# Sheet1.net
KiCad netlist of a schematic drawn in Altium Designer
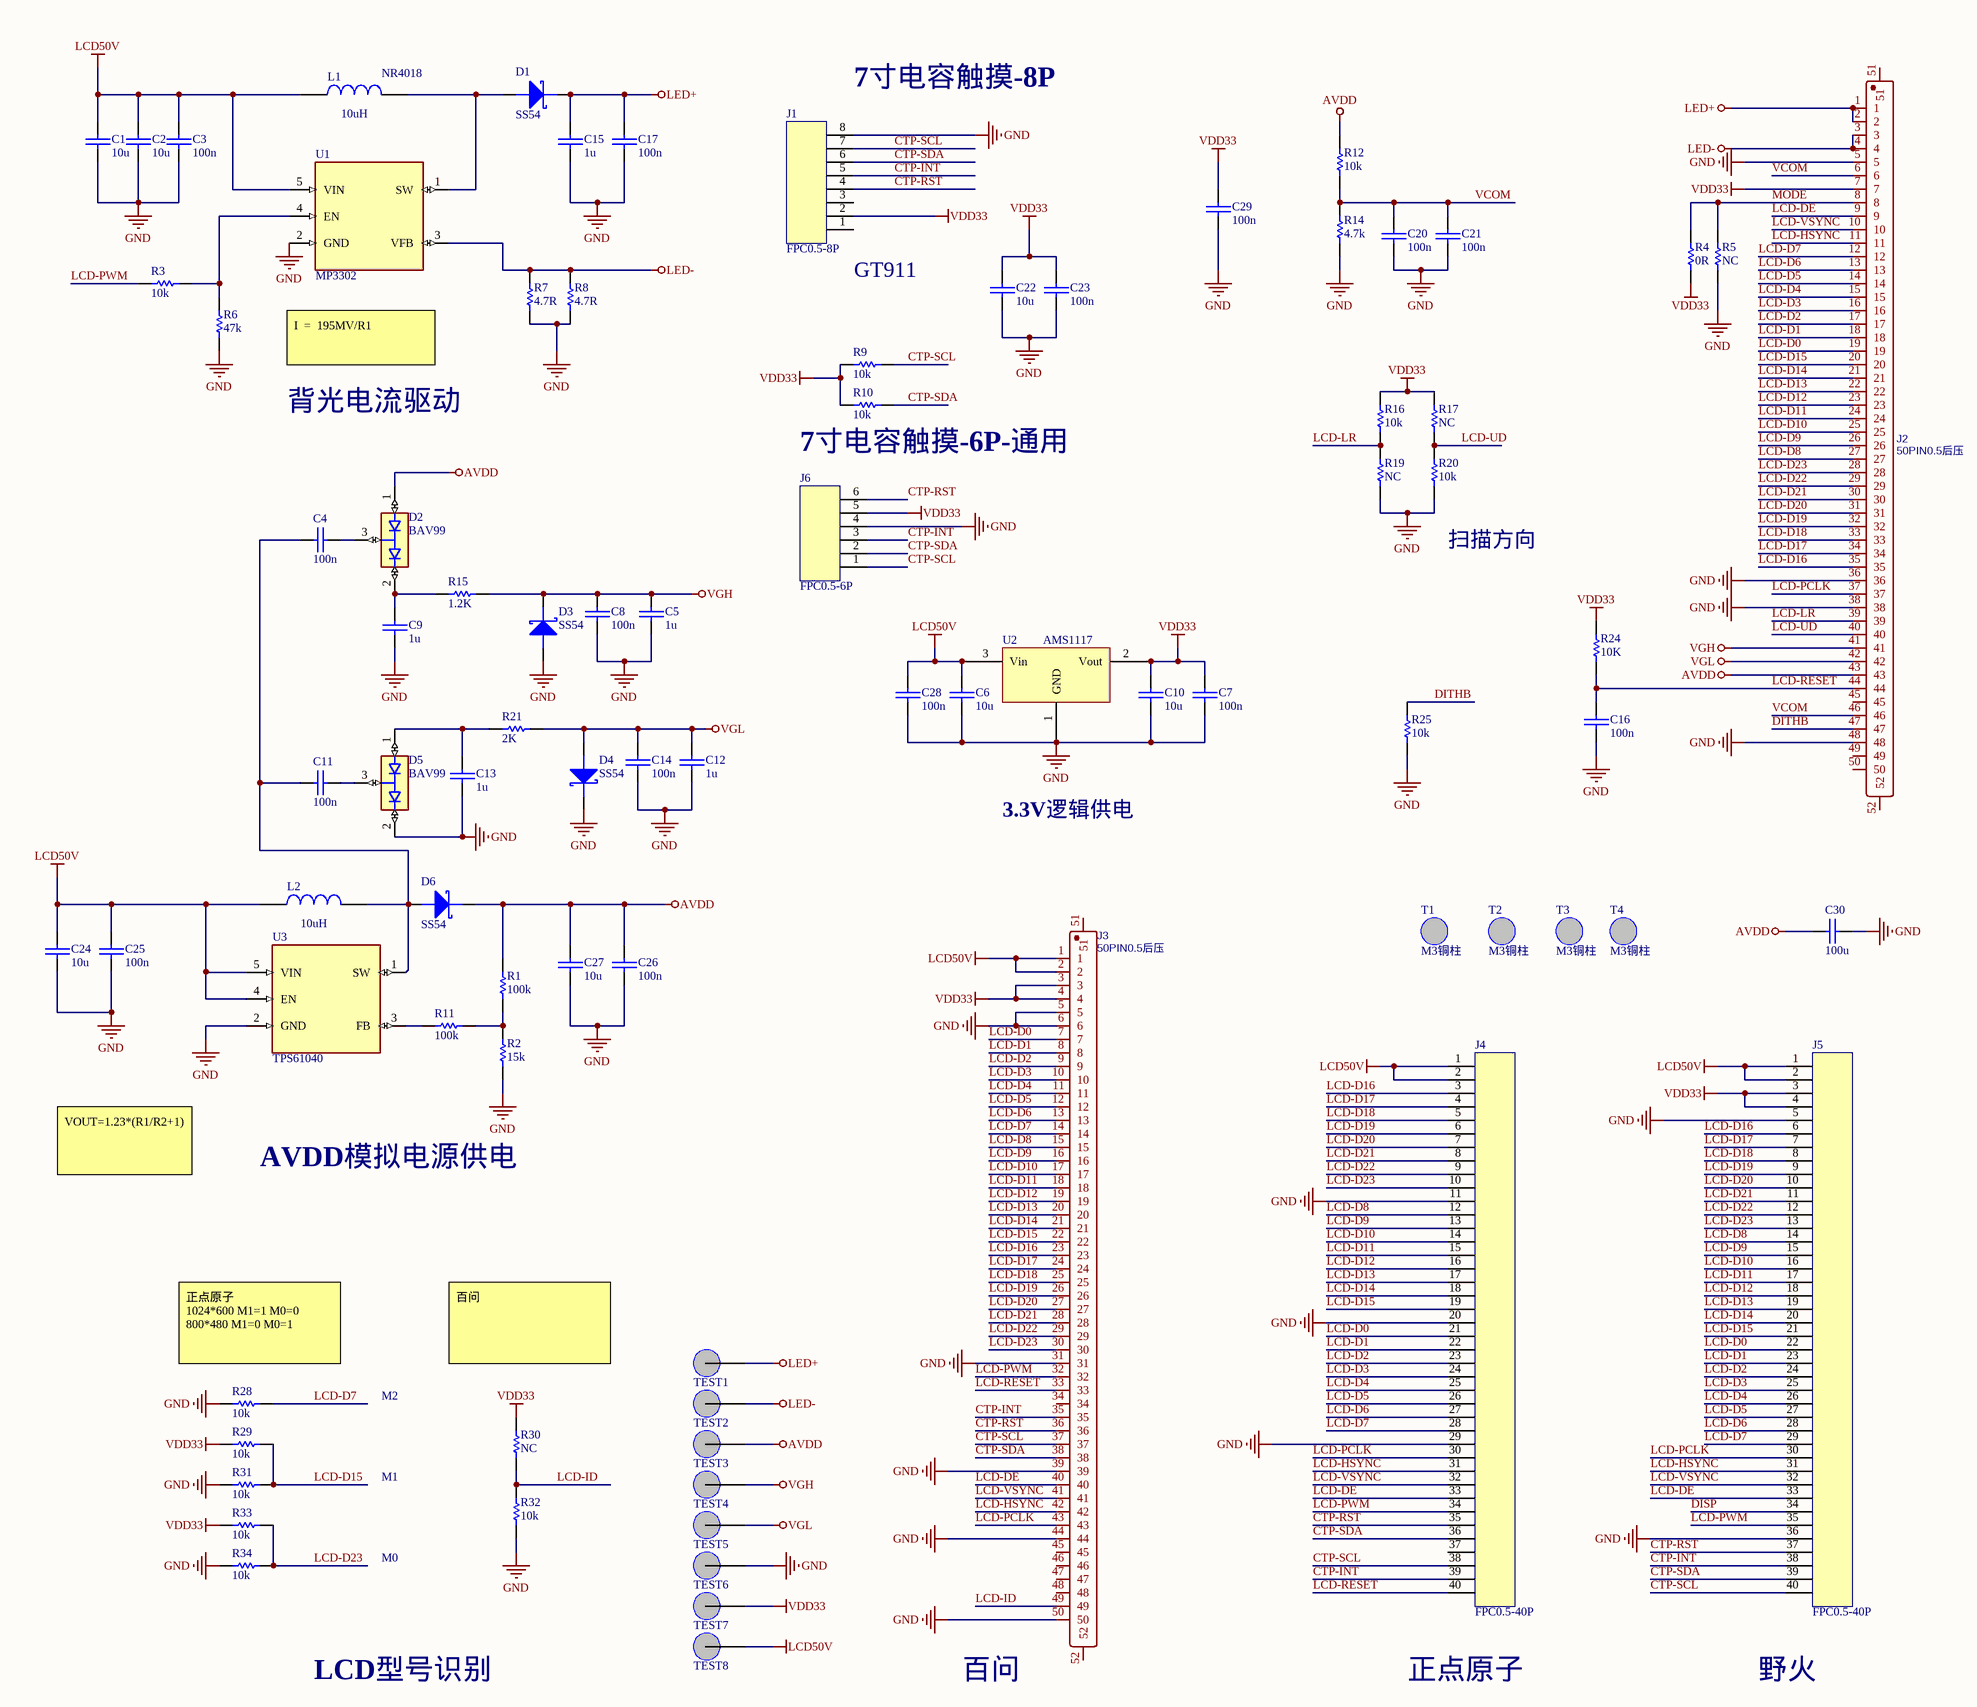
[diagram p0: Sheet1.SchDoc]

(export (version "E")
  (design (tool "Eeschema 10.0.6"))
  (components
    (comp (ref "C1")
      (value "10u")
      (footprint "0603C")
      (description "无极性电容")
      (libsource (lib "常用元件-电容") (part "CAP"))
    )
    (comp (ref "C2")
      (value "10u")
      (footprint "0603C")
      (description "无极性电容")
      (libsource (lib "常用元件-电容") (part "CAP"))
    )
    (comp (ref "C3")
      (value "100n")
      (footprint "0603C")
      (description "无极性电容")
      (libsource (lib "常用元件-电容") (part "CAP"))
    )
    (comp (ref "C4")
      (value "100n")
      (footprint "0603C")
      (description "无极性电容")
      (libsource (lib "常用元件-电容") (part "CAP"))
    )
    (comp (ref "C5")
      (value "1u")
      (footprint "0603C")
      (description "无极性电容")
      (libsource (lib "常用元件-电容") (part "CAP"))
    )
    (comp (ref "C6")
      (value "10u")
      (footprint "0603C")
      (description "无极性电容")
      (libsource (lib "常用元件-电容") (part "CAP"))
    )
    (comp (ref "C7")
      (value "100n")
      (footprint "0603C")
      (description "无极性电容")
      (libsource (lib "常用元件-电容") (part "CAP"))
    )
    (comp (ref "C8")
      (value "100n")
      (footprint "0603C")
      (description "无极性电容")
      (libsource (lib "常用元件-电容") (part "CAP"))
    )
    (comp (ref "C9")
      (value "1u")
      (footprint "0603C")
      (description "无极性电容")
      (libsource (lib "常用元件-电容") (part "CAP"))
    )
    (comp (ref "C10")
      (value "10u")
      (footprint "0603C")
      (description "无极性电容")
      (libsource (lib "常用元件-电容") (part "CAP"))
    )
    (comp (ref "C11")
      (value "100n")
      (footprint "0603C")
      (description "无极性电容")
      (libsource (lib "常用元件-电容") (part "CAP"))
    )
    (comp (ref "C12")
      (value "1u")
      (footprint "0603C")
      (description "无极性电容")
      (libsource (lib "常用元件-电容") (part "CAP"))
    )
    (comp (ref "C13")
      (value "1u")
      (footprint "0603C")
      (description "无极性电容")
      (libsource (lib "常用元件-电容") (part "CAP"))
    )
    (comp (ref "C14")
      (value "100n")
      (footprint "0603C")
      (description "无极性电容")
      (libsource (lib "常用元件-电容") (part "CAP"))
    )
    (comp (ref "C15")
      (value "1u")
      (footprint "0603C")
      (description "无极性电容")
      (libsource (lib "常用元件-电容") (part "CAP"))
    )
    (comp (ref "C16")
      (value "100n")
      (footprint "0603C")
      (description "无极性电容")
      (libsource (lib "常用元件-电容") (part "CAP"))
    )
    (comp (ref "C17")
      (value "100n")
      (footprint "0603C")
      (description "无极性电容")
      (libsource (lib "常用元件-电容") (part "CAP"))
    )
    (comp (ref "C20")
      (value "100n")
      (footprint "0603C")
      (description "无极性电容")
      (libsource (lib "常用元件-电容") (part "CAP"))
    )
    (comp (ref "C21")
      (value "100n")
      (footprint "0603C")
      (description "无极性电容")
      (libsource (lib "常用元件-电容") (part "CAP"))
    )
    (comp (ref "C22")
      (value "10u")
      (footprint "0603C")
      (description "无极性电容")
      (libsource (lib "常用元件-电容") (part "CAP"))
    )
    (comp (ref "C23")
      (value "100n")
      (footprint "0603C")
      (description "无极性电容")
      (libsource (lib "常用元件-电容") (part "CAP"))
    )
    (comp (ref "C24")
      (value "10u")
      (footprint "0603C")
      (description "无极性电容")
      (libsource (lib "常用元件-电容") (part "CAP"))
    )
    (comp (ref "C25")
      (value "100n")
      (footprint "0603C")
      (description "无极性电容")
      (libsource (lib "常用元件-电容") (part "CAP"))
    )
    (comp (ref "C26")
      (value "100n")
      (footprint "0603C")
      (description "无极性电容")
      (libsource (lib "常用元件-电容") (part "CAP"))
    )
    (comp (ref "C27")
      (value "10u")
      (footprint "0603C")
      (description "无极性电容")
      (libsource (lib "常用元件-电容") (part "CAP"))
    )
    (comp (ref "C28")
      (value "100n")
      (footprint "0603C")
      (description "无极性电容")
      (libsource (lib "常用元件-电容") (part "CAP"))
    )
    (comp (ref "C29")
      (value "100n")
      (footprint "0603C")
      (description "无极性电容")
      (libsource (lib "常用元件-电容") (part "CAP"))
    )
    (comp (ref "C30")
      (value "100u")
      (footprint "0603C")
      (description "无极性电容")
      (libsource (lib "常用元件-电容") (part "CAP"))
    )
    (comp (ref "D1")
      (value "SS54")
      (footprint "SOD-123")
      (description "肖特基二极管")
      (libsource (lib "常用元件-二极管") (part "DIODE SCHOTTKY"))
    )
    (comp (ref "D2")
      (value "BAV99")
      (footprint "BAV99:SOT23-3")
      (fields (field (name "MF") "{'manufacturer': u'ON Semiconductor'}"))
      (libsource (lib "*") (part "BAV99"))
    )
    (comp (ref "D3")
      (value "SS54")
      (footprint "SOD-123")
      (description "肖特基二极管")
      (libsource (lib "常用元件-二极管") (part "DIODE SCHOTTKY"))
    )
    (comp (ref "D4")
      (value "SS54")
      (footprint "SOD-123")
      (description "肖特基二极管")
      (libsource (lib "常用元件-二极管") (part "DIODE SCHOTTKY"))
    )
    (comp (ref "D5")
      (value "BAV99")
      (footprint "BAV99:SOT23-3")
      (fields (field (name "MF") "{'manufacturer': u'ON Semiconductor'}"))
      (libsource (lib "*") (part "BAV99"))
    )
    (comp (ref "D6")
      (value "SS54")
      (footprint "SOD-123")
      (description "肖特基二极管")
      (libsource (lib "常用元件-二极管") (part "DIODE SCHOTTKY"))
    )
    (comp (ref "J1")
      (value "FPC0.5-8P")
      (footprint "FPC0.5-8P")
      (description "贴片")
      (libsource (lib "插接类-FPC") (part "FPC0.5-8P"))
    )
    (comp (ref "J2")
      (value "50PIN0.5后压")
      (footprint "FPC-SMD_KH-FG0.5-H2.0-50PIN")
      (fields (field (name "BOM_SUPPLIER PART") "C9900011403") (field (name "CONTRIBUTOR") "LCSC"))
      (libsource (lib "altium-import") (part "root_0_50PIN0.5后压_"))
    )
    (comp (ref "J3")
      (value "50PIN0.5后压")
      (footprint "FPC-SMD_KH-FG0.5-H2.0-50PIN")
      (fields (field (name "BOM_SUPPLIER PART") "C9900011403") (field (name "CONTRIBUTOR") "LCSC"))
      (libsource (lib "altium-import") (part "root_0_50PIN0.5后压_"))
    )
    (comp (ref "J4")
      (value "FPC0.5-40P")
      (footprint "FPC0.5-40P")
      (description "贴片")
      (libsource (lib "插接类-FPC") (part "FPC0.5-40P"))
    )
    (comp (ref "J5")
      (value "FPC0.5-40P")
      (footprint "FPC0.5-40P")
      (description "贴片")
      (libsource (lib "插接类-FPC") (part "FPC0.5-40P"))
    )
    (comp (ref "J6")
      (value "FPC0.5-6P")
      (footprint "FPC0.5-6P")
      (description "贴片")
      (libsource (lib "插接类-FPC") (part "FPC0.5-6P"))
    )
    (comp (ref "L1")
      (value "10uH")
      (footprint "CD42")
      (description "INDUCTOR")
      (libsource (lib "常用元件-电感") (part "INDUCTOR"))
    )
    (comp (ref "L2")
      (value "10uH")
      (footprint "CD42")
      (description "INDUCTOR")
      (libsource (lib "常用元件-电感") (part "INDUCTOR"))
    )
    (comp (ref "R1") (value "100k") (footprint "0603R") (libsource (lib "常用元件-电阻") (part "RES")))
    (comp (ref "R2") (value "15k") (footprint "0603R") (libsource (lib "常用元件-电阻") (part "RES")))
    (comp (ref "R3") (value "10k") (footprint "0603R") (libsource (lib "常用元件-电阻") (part "RES")))
    (comp (ref "R4") (value "0R") (footprint "0603R") (libsource (lib "常用元件-电阻") (part "RES")))
    (comp (ref "R5") (value "NC") (footprint "0603R") (libsource (lib "常用元件-电阻") (part "RES")))
    (comp (ref "R6") (value "47k") (footprint "0603R") (libsource (lib "常用元件-电阻") (part "RES")))
    (comp (ref "R7") (value "4.7R") (footprint "0603R") (libsource (lib "常用元件-电阻") (part "RES")))
    (comp (ref "R8") (value "4.7R") (footprint "0603R") (libsource (lib "常用元件-电阻") (part "RES")))
    (comp (ref "R9") (value "10k") (footprint "0603R") (libsource (lib "常用元件-电阻") (part "RES")))
    (comp (ref "R10") (value "10k") (footprint "0603R") (libsource (lib "常用元件-电阻") (part "RES")))
    (comp (ref "R11") (value "100k") (footprint "0603R") (libsource (lib "常用元件-电阻") (part "RES")))
    (comp (ref "R12") (value "10k") (footprint "0603R") (libsource (lib "常用元件-电阻") (part "RES")))
    (comp (ref "R14") (value "4.7k") (footprint "0603R") (libsource (lib "常用元件-电阻") (part "RES")))
    (comp (ref "R15") (value "1.2K") (footprint "0603R") (libsource (lib "常用元件-电阻") (part "RES")))
    (comp (ref "R16") (value "10k") (footprint "0603R") (libsource (lib "常用元件-电阻") (part "RES")))
    (comp (ref "R17") (value "NC") (footprint "0603R") (libsource (lib "常用元件-电阻") (part "RES")))
    (comp (ref "R19") (value "NC") (footprint "0603R") (libsource (lib "常用元件-电阻") (part "RES")))
    (comp (ref "R20") (value "10k") (footprint "0603R") (libsource (lib "常用元件-电阻") (part "RES")))
    (comp (ref "R21") (value "2K") (footprint "0603R") (libsource (lib "常用元件-电阻") (part "RES")))
    (comp (ref "R24") (value "10K") (footprint "0603R") (libsource (lib "常用元件-电阻") (part "RES")))
    (comp (ref "R25") (value "10k") (footprint "0603R") (libsource (lib "常用元件-电阻") (part "RES")))
    (comp (ref "R28") (value "10k") (footprint "0603R") (libsource (lib "常用元件-电阻") (part "RES")))
    (comp (ref "R29") (value "10k") (footprint "0603R") (libsource (lib "常用元件-电阻") (part "RES")))
    (comp (ref "R30") (value "NC") (footprint "0603R") (libsource (lib "常用元件-电阻") (part "RES")))
    (comp (ref "R31") (value "10k") (footprint "0603R") (libsource (lib "常用元件-电阻") (part "RES")))
    (comp (ref "R32") (value "10k") (footprint "0603R") (libsource (lib "常用元件-电阻") (part "RES")))
    (comp (ref "R33") (value "10k") (footprint "0603R") (libsource (lib "常用元件-电阻") (part "RES")))
    (comp (ref "R34") (value "10k") (footprint "0603R") (libsource (lib "常用元件-电阻") (part "RES")))
    (comp (ref "T1") (value "M3铜柱") (footprint "M3 单孔") (libsource (lib "M3铜柱") (part "M3铜柱")))
    (comp (ref "T2") (value "M3铜柱") (footprint "M3 单孔") (libsource (lib "M3铜柱") (part "M3铜柱")))
    (comp (ref "T3") (value "M3铜柱") (footprint "M3 单孔") (libsource (lib "M3铜柱") (part "M3铜柱")))
    (comp (ref "T4") (value "M3铜柱") (footprint "M3 单孔") (libsource (lib "M3铜柱") (part "M3铜柱")))
    (comp (ref "TEST1")
      (value "TEST")
      (footprint "TEST TP1.4_G")
      (description "测试针")
      (fields (field (name "版权归属") "源创客"))
      (libsource (lib "测试类-测试针") (part "TEST"))
    )
    (comp (ref "TEST2")
      (value "TEST")
      (footprint "TEST TP1.4_G")
      (description "测试针")
      (fields (field (name "版权归属") "源创客"))
      (libsource (lib "测试类-测试针") (part "TEST"))
    )
    (comp (ref "TEST3")
      (value "TEST")
      (footprint "TEST TP1.4_G")
      (description "测试针")
      (fields (field (name "版权归属") "源创客"))
      (libsource (lib "测试类-测试针") (part "TEST"))
    )
    (comp (ref "TEST4")
      (value "TEST")
      (footprint "TEST TP1.4_G")
      (description "测试针")
      (fields (field (name "版权归属") "源创客"))
      (libsource (lib "测试类-测试针") (part "TEST"))
    )
    (comp (ref "TEST5")
      (value "TEST")
      (footprint "TEST TP1.4_G")
      (description "测试针")
      (fields (field (name "版权归属") "源创客"))
      (libsource (lib "测试类-测试针") (part "TEST"))
    )
    (comp (ref "TEST6")
      (value "TEST")
      (footprint "TEST TP1.4_G")
      (description "测试针")
      (fields (field (name "版权归属") "源创客"))
      (libsource (lib "测试类-测试针") (part "TEST"))
    )
    (comp (ref "TEST7")
      (value "TEST")
      (footprint "TEST TP1.4_G")
      (description "测试针")
      (fields (field (name "版权归属") "源创客"))
      (libsource (lib "测试类-测试针") (part "TEST"))
    )
    (comp (ref "TEST8")
      (value "TEST")
      (footprint "TEST TP1.4_G")
      (description "测试针")
      (fields (field (name "版权归属") "源创客"))
      (libsource (lib "测试类-测试针") (part "TEST"))
    )
    (comp (ref "U1")
      (value "MP3302")
      (footprint "SOT95P280X100-5N")
      (fields
        (field (name "MP") "TPS563201DDCR")
        (field (name "MF") "{'manufacturer': u'Texas Instruments'}")
      )
      (libsource (lib "MP3302") (part "MP3302"))
    )
    (comp (ref "U2")
      (value "AMS1117")
      (footprint "SOT223")
      (description "三端稳压芯片")
      (libsource (lib "芯片-电源芯片") (part "AMS1117"))
    )
    (comp (ref "U3")
      (value "TPS61040")
      (footprint "SOT95P280X100-5N")
      (fields
        (field (name "MP") "TPS563201DDCR")
        (field (name "MF") "{'manufacturer': u'Texas Instruments'}")
      )
      (libsource (lib "MP1541") (part "MP1541"))
    )
  )
  (nets
    (net (code "1") (name "/CTP-INT") (class "Default")
      (node (ref "J1") (pin "5") (pinfunction "5_5") (pintype "passive"))
      (node (ref "J3") (pin "35") (pinfunction "35_35") (pintype "passive"))
      (node (ref "J4") (pin "39") (pinfunction "39_39") (pintype "passive"))
      (node (ref "J5") (pin "38") (pinfunction "38_38") (pintype "passive"))
      (node (ref "J6") (pin "3") (pinfunction "3_3") (pintype "passive"))
    )
    (net (code "2") (name "/CTP-RST") (class "Default")
      (node (ref "J1") (pin "4") (pinfunction "4_4") (pintype "passive"))
      (node (ref "J3") (pin "36") (pinfunction "36_36") (pintype "passive"))
      (node (ref "J4") (pin "35") (pinfunction "35_35") (pintype "passive"))
      (node (ref "J5") (pin "37") (pinfunction "37_37") (pintype "passive"))
      (node (ref "J6") (pin "6") (pinfunction "6_6") (pintype "passive"))
    )
    (net (code "3") (name "/CTP-SCL") (class "Default")
      (node (ref "J1") (pin "7") (pinfunction "7_7") (pintype "passive"))
      (node (ref "J3") (pin "37") (pinfunction "37_37") (pintype "passive"))
      (node (ref "J4") (pin "38") (pinfunction "38_38") (pintype "passive"))
      (node (ref "J5") (pin "40") (pinfunction "40_40") (pintype "passive"))
      (node (ref "J6") (pin "1") (pinfunction "1_1") (pintype "passive"))
      (node (ref "R9") (pin "1") (pinfunction "1_1") (pintype "passive"))
    )
    (net (code "4") (name "/CTP-SDA") (class "Default")
      (node (ref "J1") (pin "6") (pinfunction "6_6") (pintype "passive"))
      (node (ref "J3") (pin "38") (pinfunction "38_38") (pintype "passive"))
      (node (ref "J4") (pin "36") (pinfunction "36_36") (pintype "passive"))
      (node (ref "J5") (pin "39") (pinfunction "39_39") (pintype "passive"))
      (node (ref "J6") (pin "2") (pinfunction "2_2") (pintype "passive"))
      (node (ref "R10") (pin "1") (pinfunction "1_1") (pintype "passive"))
    )
    (net (code "5") (name "/DISP") (class "Default")
      (node (ref "J5") (pin "34") (pinfunction "34_34") (pintype "passive"))
    )
    (net (code "6") (name "/DITHB") (class "Default")
      (node (ref "J2") (pin "47") (pinfunction "47_47") (pintype "passive"))
      (node (ref "R25") (pin "1") (pinfunction "1_1") (pintype "passive"))
    )
    (net (code "7") (name "/LCD-D0") (class "Default")
      (node (ref "J2") (pin "19") (pinfunction "19_19") (pintype "passive"))
      (node (ref "J3") (pin "7") (pinfunction "7_7") (pintype "passive"))
      (node (ref "J4") (pin "21") (pinfunction "21_21") (pintype "passive"))
      (node (ref "J5") (pin "22") (pinfunction "22_22") (pintype "passive"))
    )
    (net (code "8") (name "/LCD-D1") (class "Default")
      (node (ref "J2") (pin "18") (pinfunction "18_18") (pintype "passive"))
      (node (ref "J3") (pin "8") (pinfunction "8_8") (pintype "passive"))
      (node (ref "J4") (pin "22") (pinfunction "22_22") (pintype "passive"))
      (node (ref "J5") (pin "23") (pinfunction "23_23") (pintype "passive"))
    )
    (net (code "9") (name "/LCD-D2") (class "Default")
      (node (ref "J2") (pin "17") (pinfunction "17_17") (pintype "passive"))
      (node (ref "J3") (pin "9") (pinfunction "9_9") (pintype "passive"))
      (node (ref "J4") (pin "23") (pinfunction "23_23") (pintype "passive"))
      (node (ref "J5") (pin "24") (pinfunction "24_24") (pintype "passive"))
    )
    (net (code "10") (name "/LCD-D3") (class "Default")
      (node (ref "J2") (pin "16") (pinfunction "16_16") (pintype "passive"))
      (node (ref "J3") (pin "10") (pinfunction "10_10") (pintype "passive"))
      (node (ref "J4") (pin "24") (pinfunction "24_24") (pintype "passive"))
      (node (ref "J5") (pin "25") (pinfunction "25_25") (pintype "passive"))
    )
    (net (code "11") (name "/LCD-D4") (class "Default")
      (node (ref "J2") (pin "15") (pinfunction "15_15") (pintype "passive"))
      (node (ref "J3") (pin "11") (pinfunction "11_11") (pintype "passive"))
      (node (ref "J4") (pin "25") (pinfunction "25_25") (pintype "passive"))
      (node (ref "J5") (pin "26") (pinfunction "26_26") (pintype "passive"))
    )
    (net (code "12") (name "/LCD-D5") (class "Default")
      (node (ref "J2") (pin "14") (pinfunction "14_14") (pintype "passive"))
      (node (ref "J3") (pin "12") (pinfunction "12_12") (pintype "passive"))
      (node (ref "J4") (pin "26") (pinfunction "26_26") (pintype "passive"))
      (node (ref "J5") (pin "27") (pinfunction "27_27") (pintype "passive"))
    )
    (net (code "13") (name "/LCD-D6") (class "Default")
      (node (ref "J2") (pin "13") (pinfunction "13_13") (pintype "passive"))
      (node (ref "J3") (pin "13") (pinfunction "13_13") (pintype "passive"))
      (node (ref "J4") (pin "27") (pinfunction "27_27") (pintype "passive"))
      (node (ref "J5") (pin "28") (pinfunction "28_28") (pintype "passive"))
    )
    (net (code "14") (name "/LCD-D7") (class "Default")
      (node (ref "J2") (pin "12") (pinfunction "12_12") (pintype "passive"))
      (node (ref "J3") (pin "14") (pinfunction "14_14") (pintype "passive"))
      (node (ref "J4") (pin "28") (pinfunction "28_28") (pintype "passive"))
      (node (ref "J5") (pin "29") (pinfunction "29_29") (pintype "passive"))
      (node (ref "R28") (pin "2") (pinfunction "2_2") (pintype "passive"))
    )
    (net (code "15") (name "/LCD-D8") (class "Default")
      (node (ref "J2") (pin "27") (pinfunction "27_27") (pintype "passive"))
      (node (ref "J3") (pin "15") (pinfunction "15_15") (pintype "passive"))
      (node (ref "J4") (pin "12") (pinfunction "12_12") (pintype "passive"))
      (node (ref "J5") (pin "14") (pinfunction "14_14") (pintype "passive"))
    )
    (net (code "16") (name "/LCD-D9") (class "Default")
      (node (ref "J2") (pin "26") (pinfunction "26_26") (pintype "passive"))
      (node (ref "J3") (pin "16") (pinfunction "16_16") (pintype "passive"))
      (node (ref "J4") (pin "13") (pinfunction "13_13") (pintype "passive"))
      (node (ref "J5") (pin "15") (pinfunction "15_15") (pintype "passive"))
    )
    (net (code "17") (name "/LCD-D10") (class "Default")
      (node (ref "J2") (pin "25") (pinfunction "25_25") (pintype "passive"))
      (node (ref "J3") (pin "17") (pinfunction "17_17") (pintype "passive"))
      (node (ref "J4") (pin "14") (pinfunction "14_14") (pintype "passive"))
      (node (ref "J5") (pin "16") (pinfunction "16_16") (pintype "passive"))
    )
    (net (code "18") (name "/LCD-D11") (class "Default")
      (node (ref "J2") (pin "24") (pinfunction "24_24") (pintype "passive"))
      (node (ref "J3") (pin "18") (pinfunction "18_18") (pintype "passive"))
      (node (ref "J4") (pin "15") (pinfunction "15_15") (pintype "passive"))
      (node (ref "J5") (pin "17") (pinfunction "17_17") (pintype "passive"))
    )
    (net (code "19") (name "/LCD-D12") (class "Default")
      (node (ref "J2") (pin "23") (pinfunction "23_23") (pintype "passive"))
      (node (ref "J3") (pin "19") (pinfunction "19_19") (pintype "passive"))
      (node (ref "J4") (pin "16") (pinfunction "16_16") (pintype "passive"))
      (node (ref "J5") (pin "18") (pinfunction "18_18") (pintype "passive"))
    )
    (net (code "20") (name "/LCD-D13") (class "Default")
      (node (ref "J2") (pin "22") (pinfunction "22_22") (pintype "passive"))
      (node (ref "J3") (pin "20") (pinfunction "20_20") (pintype "passive"))
      (node (ref "J4") (pin "17") (pinfunction "17_17") (pintype "passive"))
      (node (ref "J5") (pin "19") (pinfunction "19_19") (pintype "passive"))
    )
    (net (code "21") (name "/LCD-D14") (class "Default")
      (node (ref "J2") (pin "21") (pinfunction "21_21") (pintype "passive"))
      (node (ref "J3") (pin "21") (pinfunction "21_21") (pintype "passive"))
      (node (ref "J4") (pin "18") (pinfunction "18_18") (pintype "passive"))
      (node (ref "J5") (pin "20") (pinfunction "20_20") (pintype "passive"))
    )
    (net (code "22") (name "/LCD-D15") (class "Default")
      (node (ref "J2") (pin "20") (pinfunction "20_20") (pintype "passive"))
      (node (ref "J3") (pin "22") (pinfunction "22_22") (pintype "passive"))
      (node (ref "J4") (pin "19") (pinfunction "19_19") (pintype "passive"))
      (node (ref "J5") (pin "21") (pinfunction "21_21") (pintype "passive"))
      (node (ref "R29") (pin "2") (pinfunction "2_2") (pintype "passive"))
      (node (ref "R31") (pin "1") (pinfunction "1_1") (pintype "passive"))
    )
    (net (code "23") (name "/LCD-D16") (class "Default")
      (node (ref "J2") (pin "35") (pinfunction "35_35") (pintype "passive"))
      (node (ref "J3") (pin "23") (pinfunction "23_23") (pintype "passive"))
      (node (ref "J4") (pin "3") (pinfunction "3_3") (pintype "passive"))
      (node (ref "J5") (pin "6") (pinfunction "6_6") (pintype "passive"))
    )
    (net (code "24") (name "/LCD-D17") (class "Default")
      (node (ref "J2") (pin "34") (pinfunction "34_34") (pintype "passive"))
      (node (ref "J3") (pin "24") (pinfunction "24_24") (pintype "passive"))
      (node (ref "J4") (pin "4") (pinfunction "4_4") (pintype "passive"))
      (node (ref "J5") (pin "7") (pinfunction "7_7") (pintype "passive"))
    )
    (net (code "25") (name "/LCD-D18") (class "Default")
      (node (ref "J2") (pin "33") (pinfunction "33_33") (pintype "passive"))
      (node (ref "J3") (pin "25") (pinfunction "25_25") (pintype "passive"))
      (node (ref "J4") (pin "5") (pinfunction "5_5") (pintype "passive"))
      (node (ref "J5") (pin "8") (pinfunction "8_8") (pintype "passive"))
    )
    (net (code "26") (name "/LCD-D19") (class "Default")
      (node (ref "J2") (pin "32") (pinfunction "32_32") (pintype "passive"))
      (node (ref "J3") (pin "26") (pinfunction "26_26") (pintype "passive"))
      (node (ref "J4") (pin "6") (pinfunction "6_6") (pintype "passive"))
      (node (ref "J5") (pin "9") (pinfunction "9_9") (pintype "passive"))
    )
    (net (code "27") (name "/LCD-D20") (class "Default")
      (node (ref "J2") (pin "31") (pinfunction "31_31") (pintype "passive"))
      (node (ref "J3") (pin "27") (pinfunction "27_27") (pintype "passive"))
      (node (ref "J4") (pin "7") (pinfunction "7_7") (pintype "passive"))
      (node (ref "J5") (pin "10") (pinfunction "10_10") (pintype "passive"))
    )
    (net (code "28") (name "/LCD-D21") (class "Default")
      (node (ref "J2") (pin "30") (pinfunction "30_30") (pintype "passive"))
      (node (ref "J3") (pin "28") (pinfunction "28_28") (pintype "passive"))
      (node (ref "J4") (pin "8") (pinfunction "8_8") (pintype "passive"))
      (node (ref "J5") (pin "11") (pinfunction "11_11") (pintype "passive"))
    )
    (net (code "29") (name "/LCD-D22") (class "Default")
      (node (ref "J2") (pin "29") (pinfunction "29_29") (pintype "passive"))
      (node (ref "J3") (pin "29") (pinfunction "29_29") (pintype "passive"))
      (node (ref "J4") (pin "9") (pinfunction "9_9") (pintype "passive"))
      (node (ref "J5") (pin "12") (pinfunction "12_12") (pintype "passive"))
    )
    (net (code "30") (name "/LCD-D23") (class "Default")
      (node (ref "J2") (pin "28") (pinfunction "28_28") (pintype "passive"))
      (node (ref "J3") (pin "30") (pinfunction "30_30") (pintype "passive"))
      (node (ref "J4") (pin "10") (pinfunction "10_10") (pintype "passive"))
      (node (ref "J5") (pin "13") (pinfunction "13_13") (pintype "passive"))
      (node (ref "R33") (pin "2") (pinfunction "2_2") (pintype "passive"))
      (node (ref "R34") (pin "1") (pinfunction "1_1") (pintype "passive"))
    )
    (net (code "31") (name "/LCD-DE") (class "Default")
      (node (ref "J2") (pin "9") (pinfunction "9_9") (pintype "passive"))
      (node (ref "J3") (pin "40") (pinfunction "40_40") (pintype "passive"))
      (node (ref "J4") (pin "33") (pinfunction "33_33") (pintype "passive"))
      (node (ref "J5") (pin "33") (pinfunction "33_33") (pintype "passive"))
    )
    (net (code "32") (name "/LCD-HSYNC") (class "Default")
      (node (ref "J2") (pin "11") (pinfunction "11_11") (pintype "passive"))
      (node (ref "J3") (pin "42") (pinfunction "42_42") (pintype "passive"))
      (node (ref "J4") (pin "31") (pinfunction "31_31") (pintype "passive"))
      (node (ref "J5") (pin "31") (pinfunction "31_31") (pintype "passive"))
    )
    (net (code "33") (name "/LCD-ID") (class "Default")
      (node (ref "J3") (pin "49") (pinfunction "49_49") (pintype "passive"))
      (node (ref "R30") (pin "2") (pinfunction "2_2") (pintype "passive"))
      (node (ref "R32") (pin "2") (pinfunction "2_2") (pintype "passive"))
    )
    (net (code "34") (name "/LCD-LR") (class "Default")
      (node (ref "J2") (pin "39") (pinfunction "39_39") (pintype "passive"))
      (node (ref "R16") (pin "2") (pinfunction "2_2") (pintype "passive"))
      (node (ref "R19") (pin "1") (pinfunction "1_1") (pintype "passive"))
    )
    (net (code "35") (name "/LCD-PCLK") (class "Default")
      (node (ref "J2") (pin "37") (pinfunction "37_37") (pintype "passive"))
      (node (ref "J3") (pin "43") (pinfunction "43_43") (pintype "passive"))
      (node (ref "J4") (pin "30") (pinfunction "30_30") (pintype "passive"))
      (node (ref "J5") (pin "30") (pinfunction "30_30") (pintype "passive"))
    )
    (net (code "36") (name "/LCD-PWM") (class "Default")
      (node (ref "J3") (pin "32") (pinfunction "32_32") (pintype "passive"))
      (node (ref "J4") (pin "34") (pinfunction "34_34") (pintype "passive"))
      (node (ref "J5") (pin "35") (pinfunction "35_35") (pintype "passive"))
      (node (ref "R3") (pin "1") (pinfunction "1_1") (pintype "passive"))
    )
    (net (code "37") (name "/LCD-RESET") (class "Default")
      (node (ref "C16") (pin "2") (pinfunction "2_2") (pintype "passive"))
      (node (ref "J2") (pin "44") (pinfunction "44_44") (pintype "passive"))
      (node (ref "J3") (pin "33") (pinfunction "33_33") (pintype "passive"))
      (node (ref "J4") (pin "40") (pinfunction "40_40") (pintype "passive"))
      (node (ref "R24") (pin "2") (pinfunction "2_2") (pintype "passive"))
    )
    (net (code "38") (name "/LCD-UD") (class "Default")
      (node (ref "J2") (pin "40") (pinfunction "40_40") (pintype "passive"))
      (node (ref "R17") (pin "2") (pinfunction "2_2") (pintype "passive"))
      (node (ref "R20") (pin "1") (pinfunction "1_1") (pintype "passive"))
    )
    (net (code "39") (name "/LCD-VSYNC") (class "Default")
      (node (ref "J2") (pin "10") (pinfunction "10_10") (pintype "passive"))
      (node (ref "J3") (pin "41") (pinfunction "41_41") (pintype "passive"))
      (node (ref "J4") (pin "32") (pinfunction "32_32") (pintype "passive"))
      (node (ref "J5") (pin "32") (pinfunction "32_32") (pintype "passive"))
    )
    (net (code "40") (name "/MODE") (class "Default")
      (node (ref "J2") (pin "8") (pinfunction "8_8") (pintype "passive"))
      (node (ref "R4") (pin "1") (pinfunction "1_1") (pintype "passive"))
      (node (ref "R5") (pin "1") (pinfunction "1_1") (pintype "passive"))
    )
    (net (code "41") (name "/VCOM") (class "Default")
      (node (ref "C20") (pin "2") (pinfunction "2_2") (pintype "passive"))
      (node (ref "C21") (pin "2") (pinfunction "2_2") (pintype "passive"))
      (node (ref "J2") (pin "46") (pinfunction "46_46") (pintype "passive"))
      (node (ref "J2") (pin "6") (pinfunction "6_6") (pintype "passive"))
      (node (ref "R12") (pin "2") (pinfunction "2_2") (pintype "passive"))
      (node (ref "R14") (pin "1") (pinfunction "1_1") (pintype "passive"))
    )
    (net (code "42") (name "AVDD") (class "Default")
      (node (ref "C26") (pin "2") (pinfunction "2_2") (pintype "passive"))
      (node (ref "C27") (pin "2") (pinfunction "2_2") (pintype "passive"))
      (node (ref "C30") (pin "1") (pinfunction "1_1") (pintype "passive"))
      (node (ref "D2") (pin "1") (pinfunction "A1_1") (pintype "bidirectional"))
      (node (ref "D6") (pin "K") (pinfunction "K_K") (pintype "passive"))
      (node (ref "J2") (pin "43") (pinfunction "43_43") (pintype "passive"))
      (node (ref "R1") (pin "1") (pinfunction "1_1") (pintype "passive"))
      (node (ref "R12") (pin "1") (pinfunction "1_1") (pintype "passive"))
      (node (ref "TEST3") (pin "1") (pinfunction "1_1") (pintype "passive"))
    )
    (net (code "43") (name "GND") (class "Default")
      (node (ref "C1") (pin "1") (pinfunction "1_1") (pintype "passive"))
      (node (ref "C10") (pin "1") (pinfunction "1_1") (pintype "passive"))
      (node (ref "C12") (pin "1") (pinfunction "1_1") (pintype "passive"))
      (node (ref "C13") (pin "2") (pinfunction "2_2") (pintype "passive"))
      (node (ref "C14") (pin "1") (pinfunction "1_1") (pintype "passive"))
      (node (ref "C15") (pin "1") (pinfunction "1_1") (pintype "passive"))
      (node (ref "C16") (pin "1") (pinfunction "1_1") (pintype "passive"))
      (node (ref "C17") (pin "1") (pinfunction "1_1") (pintype "passive"))
      (node (ref "C2") (pin "1") (pinfunction "1_1") (pintype "passive"))
      (node (ref "C20") (pin "1") (pinfunction "1_1") (pintype "passive"))
      (node (ref "C21") (pin "1") (pinfunction "1_1") (pintype "passive"))
      (node (ref "C22") (pin "1") (pinfunction "1_1") (pintype "passive"))
      (node (ref "C23") (pin "1") (pinfunction "1_1") (pintype "passive"))
      (node (ref "C24") (pin "1") (pinfunction "1_1") (pintype "passive"))
      (node (ref "C25") (pin "1") (pinfunction "1_1") (pintype "passive"))
      (node (ref "C26") (pin "1") (pinfunction "1_1") (pintype "passive"))
      (node (ref "C27") (pin "1") (pinfunction "1_1") (pintype "passive"))
      (node (ref "C28") (pin "1") (pinfunction "1_1") (pintype "passive"))
      (node (ref "C29") (pin "1") (pinfunction "1_1") (pintype "passive"))
      (node (ref "C3") (pin "1") (pinfunction "1_1") (pintype "passive"))
      (node (ref "C30") (pin "2") (pinfunction "2_2") (pintype "passive"))
      (node (ref "C5") (pin "1") (pinfunction "1_1") (pintype "passive"))
      (node (ref "C6") (pin "1") (pinfunction "1_1") (pintype "passive"))
      (node (ref "C7") (pin "1") (pinfunction "1_1") (pintype "passive"))
      (node (ref "C8") (pin "1") (pinfunction "1_1") (pintype "passive"))
      (node (ref "C9") (pin "1") (pinfunction "1_1") (pintype "passive"))
      (node (ref "D3") (pin "A") (pinfunction "A_A") (pintype "passive"))
      (node (ref "D4") (pin "K") (pinfunction "K_K") (pintype "passive"))
      (node (ref "D5") (pin "2") (pinfunction "C2_2") (pintype "bidirectional"))
      (node (ref "J1") (pin "8") (pinfunction "8_8") (pintype "passive"))
      (node (ref "J2") (pin "36") (pinfunction "36_36") (pintype "passive"))
      (node (ref "J2") (pin "38") (pinfunction "38_38") (pintype "passive"))
      (node (ref "J2") (pin "48") (pinfunction "48_48") (pintype "passive"))
      (node (ref "J2") (pin "5") (pinfunction "5_5") (pintype "passive"))
      (node (ref "J3") (pin "31") (pinfunction "31_31") (pintype "passive"))
      (node (ref "J3") (pin "39") (pinfunction "39_39") (pintype "passive"))
      (node (ref "J3") (pin "44") (pinfunction "44_44") (pintype "passive"))
      (node (ref "J3") (pin "5") (pinfunction "5_5") (pintype "passive"))
      (node (ref "J3") (pin "50") (pinfunction "50_50") (pintype "passive"))
      (node (ref "J3") (pin "6") (pinfunction "6_6") (pintype "passive"))
      (node (ref "J4") (pin "11") (pinfunction "11_11") (pintype "passive"))
      (node (ref "J4") (pin "20") (pinfunction "20_20") (pintype "passive"))
      (node (ref "J4") (pin "29") (pinfunction "29_29") (pintype "passive"))
      (node (ref "J5") (pin "36") (pinfunction "36_36") (pintype "passive"))
      (node (ref "J5") (pin "5") (pinfunction "5_5") (pintype "passive"))
      (node (ref "J6") (pin "4") (pinfunction "4_4") (pintype "passive"))
      (node (ref "R14") (pin "2") (pinfunction "2_2") (pintype "passive"))
      (node (ref "R19") (pin "2") (pinfunction "2_2") (pintype "passive"))
      (node (ref "R2") (pin "1") (pinfunction "1_1") (pintype "passive"))
      (node (ref "R20") (pin "2") (pinfunction "2_2") (pintype "passive"))
      (node (ref "R25") (pin "2") (pinfunction "2_2") (pintype "passive"))
      (node (ref "R28") (pin "1") (pinfunction "1_1") (pintype "passive"))
      (node (ref "R31") (pin "2") (pinfunction "2_2") (pintype "passive"))
      (node (ref "R32") (pin "1") (pinfunction "1_1") (pintype "passive"))
      (node (ref "R34") (pin "2") (pinfunction "2_2") (pintype "passive"))
      (node (ref "R5") (pin "2") (pinfunction "2_2") (pintype "passive"))
      (node (ref "R6") (pin "1") (pinfunction "1_1") (pintype "passive"))
      (node (ref "R7") (pin "1") (pinfunction "1_1") (pintype "passive"))
      (node (ref "R8") (pin "1") (pinfunction "1_1") (pintype "passive"))
      (node (ref "TEST6") (pin "1") (pinfunction "1_1") (pintype "passive"))
      (node (ref "U1") (pin "2") (pinfunction "GND_2") (pintype "input"))
      (node (ref "U2") (pin "1") (pinfunction "GND_1") (pintype "passive"))
      (node (ref "U3") (pin "2") (pinfunction "GND_2") (pintype "input"))
    )
    (net (code "44") (name "LCD50V") (class "Default")
      (node (ref "C1") (pin "2") (pinfunction "2_2") (pintype "passive"))
      (node (ref "C2") (pin "2") (pinfunction "2_2") (pintype "passive"))
      (node (ref "C24") (pin "2") (pinfunction "2_2") (pintype "passive"))
      (node (ref "C25") (pin "2") (pinfunction "2_2") (pintype "passive"))
      (node (ref "C28") (pin "2") (pinfunction "2_2") (pintype "passive"))
      (node (ref "C3") (pin "2") (pinfunction "2_2") (pintype "passive"))
      (node (ref "C6") (pin "2") (pinfunction "2_2") (pintype "passive"))
      (node (ref "J3") (pin "1") (pinfunction "1_1") (pintype "passive"))
      (node (ref "J3") (pin "2") (pinfunction "2_2") (pintype "passive"))
      (node (ref "J4") (pin "1") (pinfunction "1_1") (pintype "passive"))
      (node (ref "J4") (pin "2") (pinfunction "2_2") (pintype "passive"))
      (node (ref "J5") (pin "1") (pinfunction "1_1") (pintype "passive"))
      (node (ref "J5") (pin "2") (pinfunction "2_2") (pintype "passive"))
      (node (ref "L1") (pin "1") (pinfunction "1_1") (pintype "passive"))
      (node (ref "L2") (pin "1") (pinfunction "1_1") (pintype "passive"))
      (node (ref "TEST8") (pin "1") (pinfunction "1_1") (pintype "passive"))
      (node (ref "U1") (pin "5") (pinfunction "VIN_5") (pintype "input"))
      (node (ref "U2") (pin "3") (pinfunction "Vin_3") (pintype "passive"))
      (node (ref "U3") (pin "4") (pinfunction "EN_4") (pintype "input"))
      (node (ref "U3") (pin "5") (pinfunction "VIN_5") (pintype "input"))
    )
    (net (code "45") (name "LED+") (class "Default")
      (node (ref "C15") (pin "2") (pinfunction "2_2") (pintype "passive"))
      (node (ref "C17") (pin "2") (pinfunction "2_2") (pintype "passive"))
      (node (ref "D1") (pin "K") (pinfunction "K_K") (pintype "passive"))
      (node (ref "J2") (pin "1") (pinfunction "1_1") (pintype "passive"))
      (node (ref "J2") (pin "2") (pinfunction "2_2") (pintype "passive"))
      (node (ref "TEST1") (pin "1") (pinfunction "1_1") (pintype "passive"))
    )
    (net (code "46") (name "LED-") (class "Default")
      (node (ref "J2") (pin "3") (pinfunction "3_3") (pintype "passive"))
      (node (ref "J2") (pin "4") (pinfunction "4_4") (pintype "passive"))
      (node (ref "R7") (pin "2") (pinfunction "2_2") (pintype "passive"))
      (node (ref "R8") (pin "2") (pinfunction "2_2") (pintype "passive"))
      (node (ref "TEST2") (pin "1") (pinfunction "1_1") (pintype "passive"))
      (node (ref "U1") (pin "3") (pinfunction "VFB_3") (pintype "bidirectional"))
    )
    (net (code "47") (name "Net-(D2-C2)") (class "Default")
      (node (ref "C9") (pin "2") (pinfunction "2_2") (pintype "passive"))
      (node (ref "D2") (pin "2") (pinfunction "C2_2") (pintype "bidirectional"))
      (node (ref "R15") (pin "1") (pinfunction "1_1") (pintype "passive"))
    )
    (net (code "48") (name "Net-(D2-COM)") (class "Default")
      (node (ref "C4") (pin "1") (pinfunction "1_1") (pintype "passive"))
      (node (ref "D2") (pin "3") (pinfunction "COM_3") (pintype "bidirectional"))
    )
    (net (code "49") (name "Net-(D5-A1)") (class "Default")
      (node (ref "C13") (pin "1") (pinfunction "1_1") (pintype "passive"))
      (node (ref "D5") (pin "1") (pinfunction "A1_1") (pintype "bidirectional"))
      (node (ref "R21") (pin "1") (pinfunction "1_1") (pintype "passive"))
    )
    (net (code "50") (name "Net-(D5-COM)") (class "Default")
      (node (ref "C11") (pin "1") (pinfunction "1_1") (pintype "passive"))
      (node (ref "D5") (pin "3") (pinfunction "COM_3") (pintype "bidirectional"))
    )
    (net (code "51") (name "Net-(R1-Pad2)") (class "Default")
      (node (ref "R1") (pin "2") (pinfunction "2_2") (pintype "passive"))
      (node (ref "R11") (pin "2") (pinfunction "2_2") (pintype "passive"))
      (node (ref "R2") (pin "2") (pinfunction "2_2") (pintype "passive"))
    )
    (net (code "52") (name "Net-(U1-EN)") (class "Default")
      (node (ref "R3") (pin "2") (pinfunction "2_2") (pintype "passive"))
      (node (ref "R6") (pin "2") (pinfunction "2_2") (pintype "passive"))
      (node (ref "U1") (pin "4") (pinfunction "EN_4") (pintype "input"))
    )
    (net (code "53") (name "Net-(U1-SW)") (class "Default")
      (node (ref "D1") (pin "A") (pinfunction "A_A") (pintype "passive"))
      (node (ref "L1") (pin "2") (pinfunction "2_2") (pintype "passive"))
      (node (ref "U1") (pin "1") (pinfunction "SW_1") (pintype "bidirectional"))
    )
    (net (code "54") (name "Net-(U3-FB)") (class "Default")
      (node (ref "R11") (pin "1") (pinfunction "1_1") (pintype "passive"))
      (node (ref "U3") (pin "3") (pinfunction "FB_3") (pintype "bidirectional"))
    )
    (net (code "55") (name "Net-(U3-SW)") (class "Default")
      (node (ref "C11") (pin "2") (pinfunction "2_2") (pintype "passive"))
      (node (ref "C4") (pin "2") (pinfunction "2_2") (pintype "passive"))
      (node (ref "D6") (pin "A") (pinfunction "A_A") (pintype "passive"))
      (node (ref "L2") (pin "2") (pinfunction "2_2") (pintype "passive"))
      (node (ref "U3") (pin "1") (pinfunction "SW_1") (pintype "bidirectional"))
    )
    (net (code "56") (name "VDD33") (class "Default")
      (node (ref "C10") (pin "2") (pinfunction "2_2") (pintype "passive"))
      (node (ref "C22") (pin "2") (pinfunction "2_2") (pintype "passive"))
      (node (ref "C23") (pin "2") (pinfunction "2_2") (pintype "passive"))
      (node (ref "C29") (pin "2") (pinfunction "2_2") (pintype "passive"))
      (node (ref "C7") (pin "2") (pinfunction "2_2") (pintype "passive"))
      (node (ref "J1") (pin "2") (pinfunction "2_2") (pintype "passive"))
      (node (ref "J2") (pin "7") (pinfunction "7_7") (pintype "passive"))
      (node (ref "J3") (pin "3") (pinfunction "3_3") (pintype "passive"))
      (node (ref "J3") (pin "4") (pinfunction "4_4") (pintype "passive"))
      (node (ref "J5") (pin "3") (pinfunction "3_3") (pintype "passive"))
      (node (ref "J5") (pin "4") (pinfunction "4_4") (pintype "passive"))
      (node (ref "J6") (pin "5") (pinfunction "5_5") (pintype "passive"))
      (node (ref "R10") (pin "2") (pinfunction "2_2") (pintype "passive"))
      (node (ref "R16") (pin "1") (pinfunction "1_1") (pintype "passive"))
      (node (ref "R17") (pin "1") (pinfunction "1_1") (pintype "passive"))
      (node (ref "R24") (pin "1") (pinfunction "1_1") (pintype "passive"))
      (node (ref "R29") (pin "1") (pinfunction "1_1") (pintype "passive"))
      (node (ref "R30") (pin "1") (pinfunction "1_1") (pintype "passive"))
      (node (ref "R33") (pin "1") (pinfunction "1_1") (pintype "passive"))
      (node (ref "R4") (pin "2") (pinfunction "2_2") (pintype "passive"))
      (node (ref "R9") (pin "2") (pinfunction "2_2") (pintype "passive"))
      (node (ref "TEST7") (pin "1") (pinfunction "1_1") (pintype "passive"))
      (node (ref "U2") (pin "2") (pinfunction "Vout_2") (pintype "passive"))
    )
    (net (code "57") (name "VGH") (class "Default")
      (node (ref "C5") (pin "2") (pinfunction "2_2") (pintype "passive"))
      (node (ref "C8") (pin "2") (pinfunction "2_2") (pintype "passive"))
      (node (ref "D3") (pin "K") (pinfunction "K_K") (pintype "passive"))
      (node (ref "J2") (pin "41") (pinfunction "41_41") (pintype "passive"))
      (node (ref "R15") (pin "2") (pinfunction "2_2") (pintype "passive"))
      (node (ref "TEST4") (pin "1") (pinfunction "1_1") (pintype "passive"))
    )
    (net (code "58") (name "VGL") (class "Default")
      (node (ref "C12") (pin "2") (pinfunction "2_2") (pintype "passive"))
      (node (ref "C14") (pin "2") (pinfunction "2_2") (pintype "passive"))
      (node (ref "D4") (pin "A") (pinfunction "A_A") (pintype "passive"))
      (node (ref "J2") (pin "42") (pinfunction "42_42") (pintype "passive"))
      (node (ref "R21") (pin "2") (pinfunction "2_2") (pintype "passive"))
      (node (ref "TEST5") (pin "1") (pinfunction "1_1") (pintype "passive"))
    )
    (net (code "59") (name "unconnected-(J1-Pad1)") (class "Default")
      (node (ref "J1") (pin "1") (pinfunction "1_1") (pintype "passive"))
    )
    (net (code "60") (name "unconnected-(J1-Pad3)") (class "Default")
      (node (ref "J1") (pin "3") (pinfunction "3_3") (pintype "passive"))
    )
    (net (code "61") (name "unconnected-(J2-Pad45)") (class "Default")
      (node (ref "J2") (pin "45") (pinfunction "45_45") (pintype "passive"))
    )
    (net (code "62") (name "unconnected-(J2-Pad49)") (class "Default")
      (node (ref "J2") (pin "49") (pinfunction "49_49") (pintype "passive"))
    )
    (net (code "63") (name "unconnected-(J2-Pad50)") (class "Default")
      (node (ref "J2") (pin "50") (pinfunction "50_50") (pintype "passive"))
    )
    (net (code "64") (name "unconnected-(J2-Pad51)") (class "Default")
      (node (ref "J2") (pin "51") (pinfunction "51_51") (pintype "passive"))
    )
    (net (code "65") (name "unconnected-(J2-Pad52)") (class "Default")
      (node (ref "J2") (pin "52") (pinfunction "52_52") (pintype "passive"))
    )
    (net (code "66") (name "unconnected-(J3-Pad34)") (class "Default")
      (node (ref "J3") (pin "34") (pinfunction "34_34") (pintype "passive"))
    )
    (net (code "67") (name "unconnected-(J3-Pad45)") (class "Default")
      (node (ref "J3") (pin "45") (pinfunction "45_45") (pintype "passive"))
    )
    (net (code "68") (name "unconnected-(J3-Pad46)") (class "Default")
      (node (ref "J3") (pin "46") (pinfunction "46_46") (pintype "passive"))
    )
    (net (code "69") (name "unconnected-(J3-Pad47)") (class "Default")
      (node (ref "J3") (pin "47") (pinfunction "47_47") (pintype "passive"))
    )
    (net (code "70") (name "unconnected-(J3-Pad48)") (class "Default")
      (node (ref "J3") (pin "48") (pinfunction "48_48") (pintype "passive"))
    )
    (net (code "71") (name "unconnected-(J3-Pad51)") (class "Default")
      (node (ref "J3") (pin "51") (pinfunction "51_51") (pintype "passive"))
    )
    (net (code "72") (name "unconnected-(J3-Pad52)") (class "Default")
      (node (ref "J3") (pin "52") (pinfunction "52_52") (pintype "passive"))
    )
    (net (code "73") (name "unconnected-(J4-Pad37)") (class "Default")
      (node (ref "J4") (pin "37") (pinfunction "37_37") (pintype "passive"))
    )
  )
)
